# linak_lin.net
KiCad netlist of a schematic drawn in EAGLE
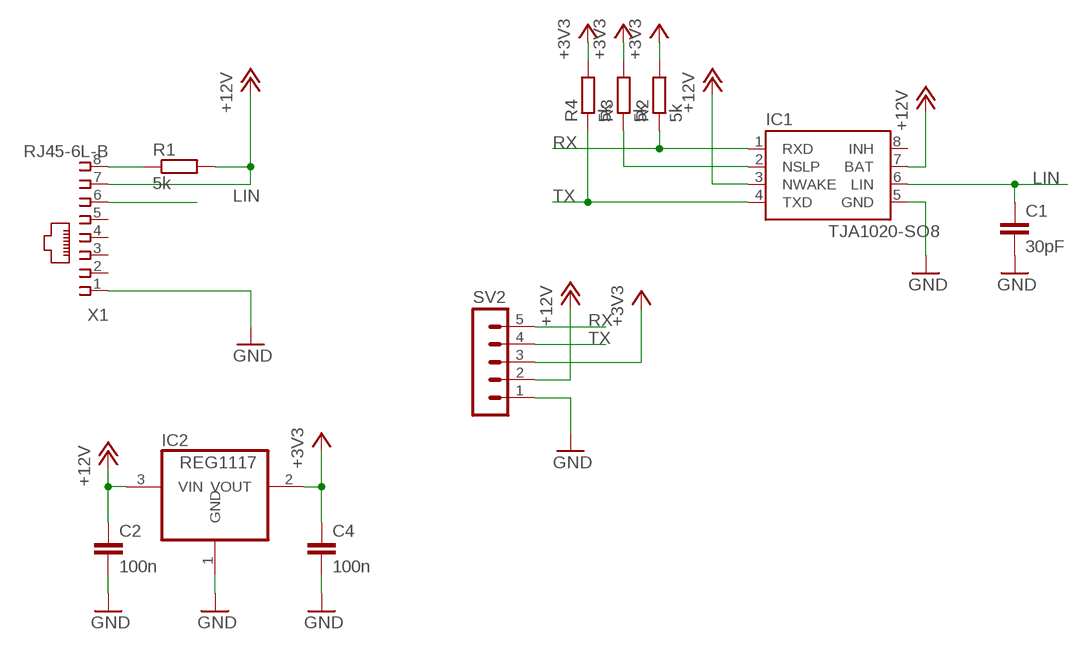
[diagram p0: schematic, sheet 1]

(export (version "E")
  (design (tool "Eeschema 10.0.6"))
  (components
    (comp (ref "C1")
      (value "30pF")
      (footprint "eagle-import:C1206")
      (libsource (lib "eagle-import") (part "C-EUC1206"))
    )
    (comp (ref "C2")
      (value "100n")
      (footprint "eagle-import:C1206")
      (libsource (lib "eagle-import") (part "C-EUC1206"))
    )
    (comp (ref "C4")
      (value "100n")
      (footprint "eagle-import:C1206")
      (libsource (lib "eagle-import") (part "C-EUC1206"))
    )
    (comp (ref "IC1")
      (value "TJA1020-SO8")
      (footprint "eagle-import:SO08")
      (libsource (lib "eagle-import") (part "TJA1020-SO8"))
    )
    (comp (ref "IC2")
      (value "REG1117")
      (footprint "eagle-import:SOT223")
      (libsource (lib "eagle-import") (part "REG1117"))
    )
    (comp (ref "R1")
      (value "5k")
      (footprint "eagle-import:R1206")
      (libsource (lib "eagle-import") (part "R-EU_R1206"))
    )
    (comp (ref "R2")
      (value "5k")
      (footprint "eagle-import:R1206")
      (libsource (lib "eagle-import") (part "R-EU_R1206"))
    )
    (comp (ref "R3")
      (value "5k")
      (footprint "eagle-import:R1206")
      (libsource (lib "eagle-import") (part "R-EU_R1206"))
    )
    (comp (ref "R4")
      (value "5k")
      (footprint "eagle-import:R1206")
      (libsource (lib "eagle-import") (part "R-EU_R1206"))
    )
    (comp (ref "SV2")
      (value "MA05-1")
      (footprint "eagle-import:MA05-1")
      (libsource (lib "eagle-import") (part "MA05-1"))
    )
    (comp (ref "X1")
      (value "RJ45-6L-B")
      (footprint "eagle-import:RJ45-NO-SHIELD")
      (libsource (lib "eagle-import") (part "RJ45-6L-B"))
    )
  )
  (nets
    (net (code "1") (name "+3V3") (class "Default")
      (node (ref "C4") (pin "1") (pinfunction "1_1") (pintype "passive"))
      (node (ref "IC2") (pin "2") (pinfunction "VOUT_2") (pintype "output"))
      (node (ref "R2") (pin "2") (pinfunction "2_2") (pintype "passive"))
      (node (ref "R3") (pin "2") (pinfunction "2_2") (pintype "passive"))
      (node (ref "R4") (pin "2") (pinfunction "2_2") (pintype "passive"))
      (node (ref "SV2") (pin "3") (pinfunction "3_3") (pintype "passive"))
    )
    (net (code "2") (name "+12V") (class "Default")
      (node (ref "C2") (pin "1") (pinfunction "1_1") (pintype "passive"))
      (node (ref "IC1") (pin "3") (pinfunction "NWAKE_3") (pintype "passive"))
      (node (ref "IC1") (pin "7") (pinfunction "BAT_7") (pintype "input"))
      (node (ref "IC2") (pin "3") (pinfunction "VIN_3") (pintype "input"))
      (node (ref "R1") (pin "2") (pinfunction "2_2") (pintype "passive"))
      (node (ref "SV2") (pin "2") (pinfunction "2_2") (pintype "passive"))
      (node (ref "X1") (pin "7") (pinfunction "7_7") (pintype "passive"))
    )
    (net (code "3") (name "/LIN") (class "Default")
      (node (ref "C1") (pin "1") (pinfunction "1_1") (pintype "passive"))
      (node (ref "IC1") (pin "6") (pinfunction "LIN_6") (pintype "input"))
      (node (ref "X1") (pin "6") (pinfunction "6_6") (pintype "passive"))
    )
    (net (code "4") (name "/RX") (class "Default")
      (node (ref "IC1") (pin "1") (pinfunction "RXD_1") (pintype "input"))
      (node (ref "R2") (pin "1") (pinfunction "1_1") (pintype "passive"))
      (node (ref "SV2") (pin "5") (pinfunction "5_5") (pintype "passive"))
    )
    (net (code "5") (name "/TX") (class "Default")
      (node (ref "IC1") (pin "4") (pinfunction "TXD_4") (pintype "passive"))
      (node (ref "R4") (pin "1") (pinfunction "1_1") (pintype "passive"))
      (node (ref "SV2") (pin "4") (pinfunction "4_4") (pintype "passive"))
    )
    (net (code "6") (name "GND") (class "Default")
      (node (ref "C1") (pin "2") (pinfunction "2_2") (pintype "passive"))
      (node (ref "C2") (pin "2") (pinfunction "2_2") (pintype "passive"))
      (node (ref "C4") (pin "2") (pinfunction "2_2") (pintype "passive"))
      (node (ref "IC1") (pin "5") (pinfunction "GND_5") (pintype "input"))
      (node (ref "IC2") (pin "1") (pinfunction "GND_1") (pintype "power_in"))
      (node (ref "SV2") (pin "1") (pinfunction "1_1") (pintype "passive"))
      (node (ref "X1") (pin "1") (pinfunction "1_1") (pintype "passive"))
    )
    (net (code "7") (name "Net-(IC1-NSLP)") (class "Default")
      (node (ref "IC1") (pin "2") (pinfunction "NSLP_2") (pintype "passive"))
      (node (ref "R3") (pin "1") (pinfunction "1_1") (pintype "passive"))
    )
    (net (code "8") (name "Net-(R1-Pad1)") (class "Default")
      (node (ref "R1") (pin "1") (pinfunction "1_1") (pintype "passive"))
      (node (ref "X1") (pin "8") (pinfunction "8_8") (pintype "passive"))
    )
    (net (code "9") (name "unconnected-(IC1-INH-Pad8)") (class "Default")
      (node (ref "IC1") (pin "8") (pinfunction "INH_8") (pintype "input"))
    )
    (net (code "10") (name "unconnected-(X1-Pad2)") (class "Default")
      (node (ref "X1") (pin "2") (pinfunction "2_2") (pintype "passive"))
    )
    (net (code "11") (name "unconnected-(X1-Pad3)") (class "Default")
      (node (ref "X1") (pin "3") (pinfunction "3_3") (pintype "passive"))
    )
    (net (code "12") (name "unconnected-(X1-Pad4)") (class "Default")
      (node (ref "X1") (pin "4") (pinfunction "4_4") (pintype "passive"))
    )
    (net (code "13") (name "unconnected-(X1-Pad5)") (class "Default")
      (node (ref "X1") (pin "5") (pinfunction "5_5") (pintype "passive"))
    )
  )
)
